# inamp.net
KiCad netlist of a schematic drawn in EAGLE
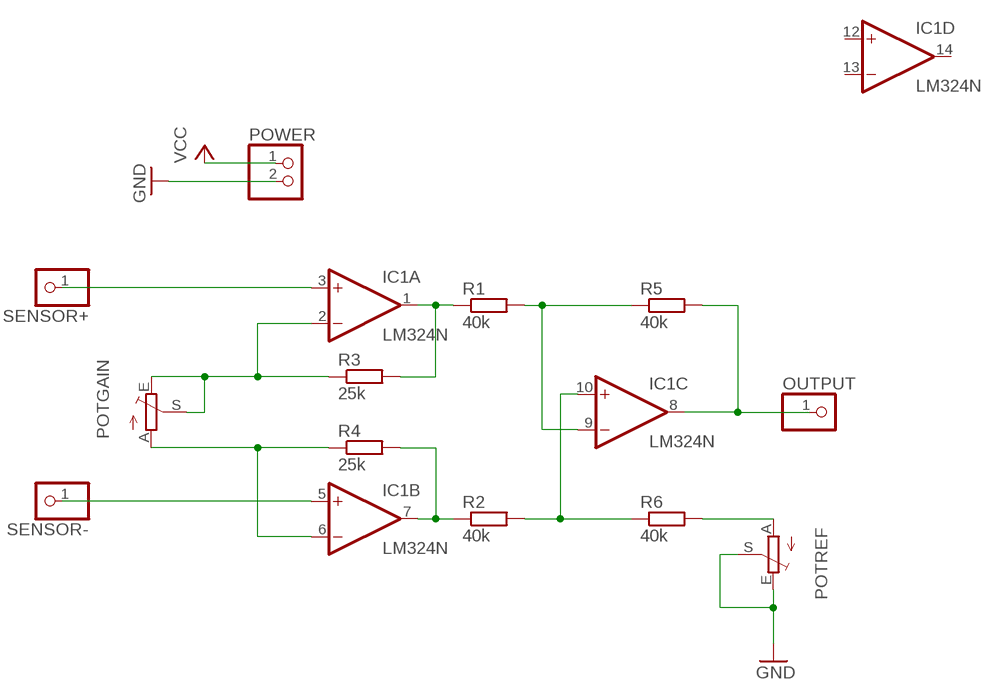
[diagram p0: schematic, sheet 1]

(export (version "E")
  (design (tool "Eeschema 10.0.6"))
  (components
    (comp (ref "IC1")
      (value "LM324N")
      (footprint "eagle-import:DIL14")
      (libsource (lib "eagle-import") (part "LM324N"))
    )
    (comp (ref "OUTPUT")
      (value "PINHD-1X1")
      (footprint "eagle-import:1X01")
      (libsource (lib "eagle-import") (part "PINHD-1X1"))
    )
    (comp (ref "POTGAIN")
      (value "TRIM_EU-CA6V")
      (footprint "eagle-import:CA6V")
      (libsource (lib "eagle-import") (part "TRIM_EU-CA6V"))
    )
    (comp (ref "POTREF")
      (value "TRIM_EU-CA6V")
      (footprint "eagle-import:CA6V")
      (libsource (lib "eagle-import") (part "TRIM_EU-CA6V"))
    )
    (comp (ref "POWER")
      (value "PINHD-1X2")
      (footprint "eagle-import:1X02")
      (libsource (lib "eagle-import") (part "PINHD-1X2"))
    )
    (comp (ref "R1")
      (value "40k")
      (footprint "eagle-import:0204_7")
      (libsource (lib "eagle-import") (part "R-EU_0204/7"))
    )
    (comp (ref "R2")
      (value "40k")
      (footprint "eagle-import:0204_7")
      (libsource (lib "eagle-import") (part "R-EU_0204/7"))
    )
    (comp (ref "R3")
      (value "25k")
      (footprint "eagle-import:0204_7")
      (libsource (lib "eagle-import") (part "R-EU_0204/7"))
    )
    (comp (ref "R4")
      (value "25k")
      (footprint "eagle-import:0204_7")
      (libsource (lib "eagle-import") (part "R-EU_0204/7"))
    )
    (comp (ref "R5")
      (value "40k")
      (footprint "eagle-import:0204_7")
      (libsource (lib "eagle-import") (part "R-EU_0204/7"))
    )
    (comp (ref "R6")
      (value "40k")
      (footprint "eagle-import:0204_7")
      (libsource (lib "eagle-import") (part "R-EU_0204/7"))
    )
    (comp (ref "SENSOR+")
      (value "PINHD-1X1")
      (footprint "eagle-import:1X01")
      (libsource (lib "eagle-import") (part "PINHD-1X1"))
    )
    (comp (ref "SENSOR-")
      (value "PINHD-1X1")
      (footprint "eagle-import:1X01")
      (libsource (lib "eagle-import") (part "PINHD-1X1"))
    )
  )
  (nets
    (net (code "1") (name "GND") (class "Default")
      (node (ref "POTREF") (pin "E") (pinfunction "E_E") (pintype "passive"))
      (node (ref "POTREF") (pin "S") (pinfunction "S_S") (pintype "passive"))
      (node (ref "POWER") (pin "2") (pinfunction "2_2") (pintype "passive"))
    )
    (net (code "2") (name "Net-(IC1A-+IN)") (class "Default")
      (node (ref "IC1") (pin "3") (pinfunction "+IN_3") (pintype "input"))
      (node (ref "SENSOR+") (pin "1") (pinfunction "1_1") (pintype "passive"))
    )
    (net (code "3") (name "Net-(IC1A--IN)") (class "Default")
      (node (ref "IC1") (pin "2") (pinfunction "-IN_2") (pintype "input"))
      (node (ref "POTGAIN") (pin "E") (pinfunction "E_E") (pintype "passive"))
      (node (ref "POTGAIN") (pin "S") (pinfunction "S_S") (pintype "passive"))
      (node (ref "R3") (pin "1") (pinfunction "1_1") (pintype "passive"))
    )
    (net (code "4") (name "Net-(IC1A-OUT)") (class "Default")
      (node (ref "IC1") (pin "1") (pinfunction "OUT_1") (pintype "output"))
      (node (ref "R1") (pin "1") (pinfunction "1_1") (pintype "passive"))
      (node (ref "R3") (pin "2") (pinfunction "2_2") (pintype "passive"))
    )
    (net (code "5") (name "Net-(IC1B-+IN)") (class "Default")
      (node (ref "IC1") (pin "5") (pinfunction "+IN_5") (pintype "input"))
      (node (ref "SENSOR-") (pin "1") (pinfunction "1_1") (pintype "passive"))
    )
    (net (code "6") (name "Net-(IC1B--IN)") (class "Default")
      (node (ref "IC1") (pin "6") (pinfunction "-IN_6") (pintype "input"))
      (node (ref "POTGAIN") (pin "A") (pinfunction "A_A") (pintype "passive"))
      (node (ref "R4") (pin "1") (pinfunction "1_1") (pintype "passive"))
    )
    (net (code "7") (name "Net-(IC1B-OUT)") (class "Default")
      (node (ref "IC1") (pin "7") (pinfunction "OUT_7") (pintype "output"))
      (node (ref "R2") (pin "1") (pinfunction "1_1") (pintype "passive"))
      (node (ref "R4") (pin "2") (pinfunction "2_2") (pintype "passive"))
    )
    (net (code "8") (name "Net-(IC1C-+IN)") (class "Default")
      (node (ref "IC1") (pin "10") (pinfunction "+IN_10") (pintype "input"))
      (node (ref "R2") (pin "2") (pinfunction "2_2") (pintype "passive"))
      (node (ref "R6") (pin "1") (pinfunction "1_1") (pintype "passive"))
    )
    (net (code "9") (name "Net-(IC1C--IN)") (class "Default")
      (node (ref "IC1") (pin "9") (pinfunction "-IN_9") (pintype "input"))
      (node (ref "R1") (pin "2") (pinfunction "2_2") (pintype "passive"))
      (node (ref "R5") (pin "1") (pinfunction "1_1") (pintype "passive"))
    )
    (net (code "10") (name "Net-(IC1C-OUT)") (class "Default")
      (node (ref "IC1") (pin "8") (pinfunction "OUT_8") (pintype "output"))
      (node (ref "OUTPUT") (pin "1") (pinfunction "1_1") (pintype "passive"))
      (node (ref "R5") (pin "2") (pinfunction "2_2") (pintype "passive"))
    )
    (net (code "11") (name "Net-(POTREF-PadA)") (class "Default")
      (node (ref "POTREF") (pin "A") (pinfunction "A_A") (pintype "passive"))
      (node (ref "R6") (pin "2") (pinfunction "2_2") (pintype "passive"))
    )
    (net (code "12") (name "VCC") (class "Default")
      (node (ref "POWER") (pin "1") (pinfunction "1_1") (pintype "passive"))
    )
    (net (code "13") (name "unconnected-(IC1D-+IN-Pad12)") (class "Default")
      (node (ref "IC1") (pin "12") (pinfunction "+IN_12") (pintype "input"))
    )
    (net (code "14") (name "unconnected-(IC1D--IN-Pad13)") (class "Default")
      (node (ref "IC1") (pin "13") (pinfunction "-IN_13") (pintype "input"))
    )
    (net (code "15") (name "unconnected-(IC1D-OUT-Pad14)") (class "Default")
      (node (ref "IC1") (pin "14") (pinfunction "OUT_14") (pintype "output"))
    )
  )
)
